# improvedThermoCoupleADC.net
KiCad netlist of a schematic drawn in EAGLE
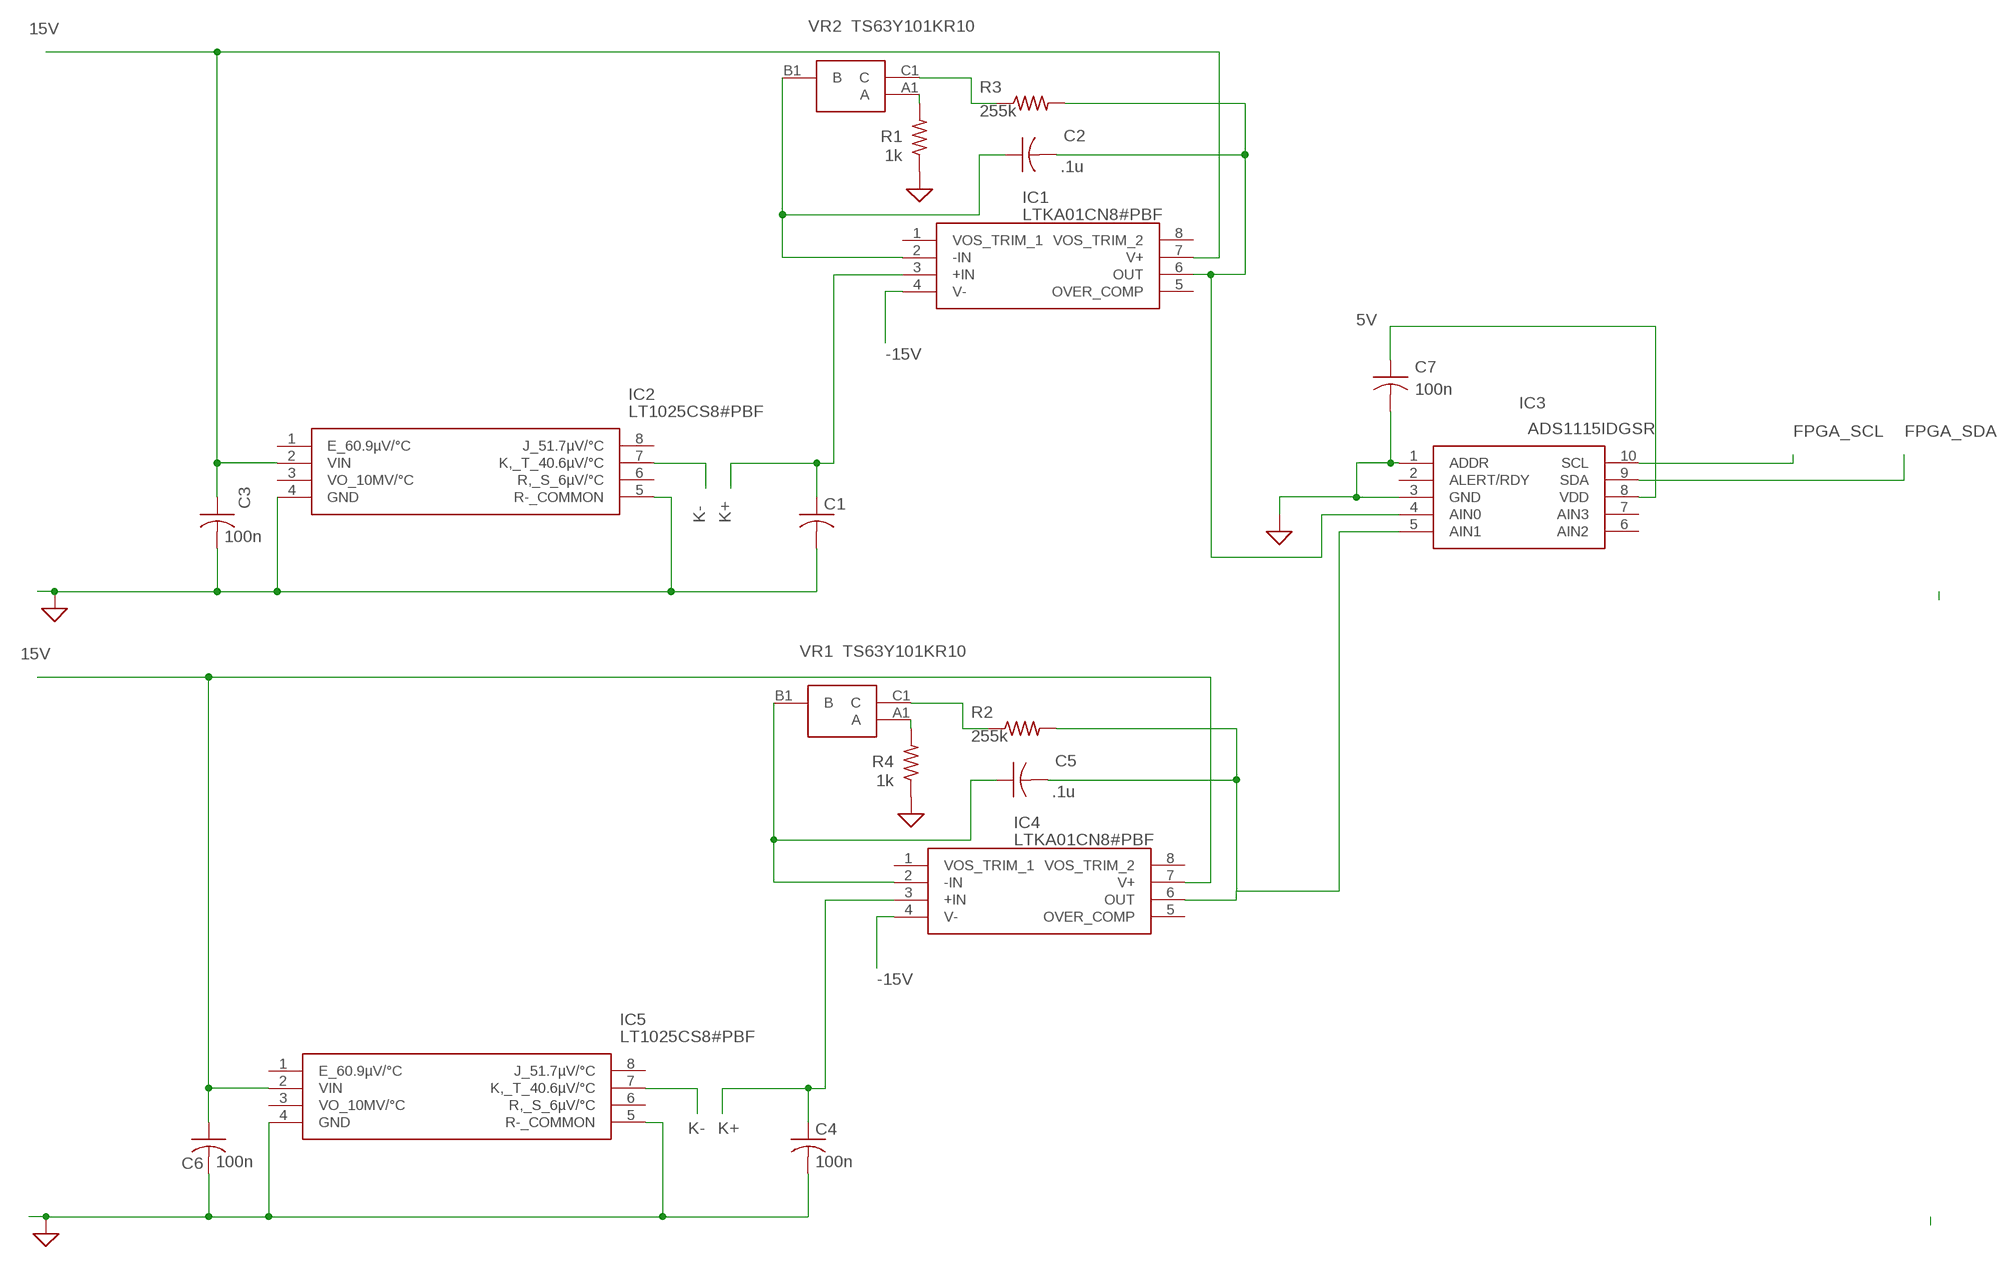
[diagram p0: schematic, sheet 1]

(export (version "E")
  (design (tool "Eeschema 10.0.6"))
  (components
    (comp (ref "C1")
      (value "C-USC0805")
      (footprint "eagle-import:C0805")
      (libsource (lib "eagle-import") (part "C-USC0805"))
    )
    (comp (ref "C2")
      (value ".1u")
      (footprint "eagle-import:C0805")
      (libsource (lib "eagle-import") (part "C-USC0805"))
    )
    (comp (ref "C3")
      (value "100n")
      (footprint "eagle-import:C0805")
      (libsource (lib "eagle-import") (part "C-USC0805"))
    )
    (comp (ref "C4")
      (value "100n")
      (footprint "eagle-import:C0805")
      (libsource (lib "eagle-import") (part "C-USC0805"))
    )
    (comp (ref "C5")
      (value ".1u")
      (footprint "eagle-import:C0805")
      (libsource (lib "eagle-import") (part "C-USC0805"))
    )
    (comp (ref "C6")
      (value "100n")
      (footprint "eagle-import:C0805")
      (libsource (lib "eagle-import") (part "C-USC0805"))
    )
    (comp (ref "C7")
      (value "100n")
      (footprint "eagle-import:C0805")
      (libsource (lib "eagle-import") (part "C-USC0805"))
    )
    (comp (ref "IC1")
      (value "LTKA01CN8#PBF")
      (footprint "eagle-import:DIP794W53P254L1016H394Q8N")
      (fields (field (name "MOUSER_PART_NUMBER") "584-LTKA01CN8#PBF"))
      (libsource (lib "eagle-import") (part "LTKA01CN8#PBF"))
    )
    (comp (ref "IC2")
      (value "LT1025CS8#PBF")
      (footprint "eagle-import:SOIC127P599X175-8N")
      (fields (field (name "MOUSER_PART_NUMBER") "584-LT1025CS8#PBF"))
      (libsource (lib "eagle-import") (part "LT1025CS8#PBF"))
    )
    (comp (ref "IC3")
      (value "ADS1115IDGSR")
      (footprint "eagle-import:SOP50P490X110-10N")
      (fields (field (name "MOUSER_PART_NUMBER") "595-ADS1115IDGSR"))
      (libsource (lib "eagle-import") (part "ADS1115IDGSR"))
    )
    (comp (ref "IC4")
      (value "LTKA01CN8#PBF")
      (footprint "eagle-import:DIP794W53P254L1016H394Q8N")
      (fields (field (name "MOUSER_PART_NUMBER") "584-LTKA01CN8#PBF"))
      (libsource (lib "eagle-import") (part "LTKA01CN8#PBF"))
    )
    (comp (ref "IC5")
      (value "LT1025CS8#PBF")
      (footprint "eagle-import:SOIC127P599X175-8N")
      (fields (field (name "MOUSER_PART_NUMBER") "584-LT1025CS8#PBF"))
      (libsource (lib "eagle-import") (part "LT1025CS8#PBF"))
    )
    (comp (ref "R1")
      (value "1k")
      (footprint "eagle-import:R0805")
      (libsource (lib "eagle-import") (part "R-US_R0805"))
    )
    (comp (ref "R2")
      (value "255k")
      (footprint "eagle-import:R0805")
      (libsource (lib "eagle-import") (part "R-US_R0805"))
    )
    (comp (ref "R3")
      (value "255k")
      (footprint "eagle-import:R0805")
      (libsource (lib "eagle-import") (part "R-US_R0805"))
    )
    (comp (ref "R4")
      (value "1k")
      (footprint "eagle-import:R0805")
      (libsource (lib "eagle-import") (part "R-US_R0805"))
    )
    (comp (ref "VR1")
      (value "TS63Y101KR10")
      (footprint "eagle-import:TS63Y203KR10")
      (fields (field (name "MOUSER_PART_NUMBER") "72-TS63Y101KR10"))
      (libsource (lib "eagle-import") (part "TS63Y101KR10"))
    )
    (comp (ref "VR2")
      (value "TS63Y101KR10")
      (footprint "eagle-import:TS63Y203KR10")
      (fields (field (name "MOUSER_PART_NUMBER") "72-TS63Y101KR10"))
      (libsource (lib "eagle-import") (part "TS63Y101KR10"))
    )
  )
  (nets
    (net (code "1") (name "/-15V") (class "Default")
      (node (ref "IC1") (pin "4") (pinfunction "V-_4") (pintype "bidirectional"))
      (node (ref "IC4") (pin "4") (pinfunction "V-_4") (pintype "bidirectional"))
    )
    (net (code "2") (name "/5V") (class "Default")
      (node (ref "C7") (pin "1") (pinfunction "1_1") (pintype "passive"))
      (node (ref "IC3") (pin "8") (pinfunction "VDD_8") (pintype "bidirectional"))
    )
    (net (code "3") (name "/15V") (class "Default")
      (node (ref "C3") (pin "1") (pinfunction "1_1") (pintype "passive"))
      (node (ref "C6") (pin "1") (pinfunction "1_1") (pintype "passive"))
      (node (ref "IC1") (pin "7") (pinfunction "V+_7") (pintype "bidirectional"))
      (node (ref "IC2") (pin "2") (pinfunction "VIN_2") (pintype "bidirectional"))
      (node (ref "IC4") (pin "7") (pinfunction "V+_7") (pintype "bidirectional"))
      (node (ref "IC5") (pin "2") (pinfunction "VIN_2") (pintype "bidirectional"))
    )
    (net (code "4") (name "/FPGA_SCL") (class "Default")
      (node (ref "IC3") (pin "10") (pinfunction "SCL_10") (pintype "bidirectional"))
    )
    (net (code "5") (name "/FPGA_SDA") (class "Default")
      (node (ref "IC3") (pin "9") (pinfunction "SDA_9") (pintype "bidirectional"))
    )
    (net (code "6") (name "/K+") (class "Default")
      (node (ref "C1") (pin "1") (pinfunction "1_1") (pintype "passive"))
      (node (ref "C4") (pin "1") (pinfunction "1_1") (pintype "passive"))
      (node (ref "IC1") (pin "3") (pinfunction "+IN_3") (pintype "bidirectional"))
      (node (ref "IC4") (pin "3") (pinfunction "+IN_3") (pintype "bidirectional"))
    )
    (net (code "7") (name "/K-") (class "Default")
      (node (ref "IC2") (pin "7") (pinfunction "K,_T_40.6µV/°C_7") (pintype "bidirectional"))
      (node (ref "IC5") (pin "7") (pinfunction "K,_T_40.6µV/°C_7") (pintype "bidirectional"))
    )
    (net (code "8") (name "Net-(IC1--IN)") (class "Default")
      (node (ref "C2") (pin "1") (pinfunction "1_1") (pintype "passive"))
      (node (ref "IC1") (pin "2") (pinfunction "-IN_2") (pintype "bidirectional"))
      (node (ref "VR2") (pin "B1") (pinfunction "B_B1") (pintype "bidirectional"))
    )
    (net (code "9") (name "Net-(IC1-OUT)") (class "Default")
      (node (ref "C2") (pin "2") (pinfunction "2_2") (pintype "passive"))
      (node (ref "IC1") (pin "6") (pinfunction "OUT_6") (pintype "bidirectional"))
      (node (ref "IC3") (pin "4") (pinfunction "AIN0_4") (pintype "bidirectional"))
      (node (ref "R3") (pin "2") (pinfunction "2_2") (pintype "passive"))
    )
    (net (code "10") (name "Net-(IC3-AIN1)") (class "Default")
      (node (ref "C5") (pin "2") (pinfunction "2_2") (pintype "passive"))
      (node (ref "IC3") (pin "5") (pinfunction "AIN1_5") (pintype "bidirectional"))
      (node (ref "IC4") (pin "6") (pinfunction "OUT_6") (pintype "bidirectional"))
      (node (ref "R2") (pin "2") (pinfunction "2_2") (pintype "passive"))
    )
    (net (code "11") (name "Net-(IC4--IN)") (class "Default")
      (node (ref "C5") (pin "1") (pinfunction "1_1") (pintype "passive"))
      (node (ref "IC4") (pin "2") (pinfunction "-IN_2") (pintype "bidirectional"))
      (node (ref "VR1") (pin "B1") (pinfunction "B_B1") (pintype "bidirectional"))
    )
    (net (code "12") (name "Net-(VR1-A)") (class "Default")
      (node (ref "R4") (pin "2") (pinfunction "2_2") (pintype "passive"))
      (node (ref "VR1") (pin "A1") (pinfunction "A_A1") (pintype "bidirectional"))
    )
    (net (code "13") (name "Net-(VR1-C)") (class "Default")
      (node (ref "R2") (pin "1") (pinfunction "1_1") (pintype "passive"))
      (node (ref "VR1") (pin "C1") (pinfunction "C_C1") (pintype "bidirectional"))
    )
    (net (code "14") (name "Net-(VR2-A)") (class "Default")
      (node (ref "R1") (pin "2") (pinfunction "2_2") (pintype "passive"))
      (node (ref "VR2") (pin "A1") (pinfunction "A_A1") (pintype "bidirectional"))
    )
    (net (code "15") (name "Net-(VR2-C)") (class "Default")
      (node (ref "R3") (pin "1") (pinfunction "1_1") (pintype "passive"))
      (node (ref "VR2") (pin "C1") (pinfunction "C_C1") (pintype "bidirectional"))
    )
    (net (code "16") (name "SUP") (class "Default")
      (node (ref "C1") (pin "2") (pinfunction "2_2") (pintype "passive"))
      (node (ref "C3") (pin "2") (pinfunction "2_2") (pintype "passive"))
      (node (ref "C4") (pin "2") (pinfunction "2_2") (pintype "passive"))
      (node (ref "C6") (pin "2") (pinfunction "2_2") (pintype "passive"))
      (node (ref "C7") (pin "2") (pinfunction "2_2") (pintype "passive"))
      (node (ref "IC2") (pin "4") (pinfunction "GND_4") (pintype "bidirectional"))
      (node (ref "IC2") (pin "5") (pinfunction "R-_COMMON_5") (pintype "bidirectional"))
      (node (ref "IC3") (pin "1") (pinfunction "ADDR_1") (pintype "bidirectional"))
      (node (ref "IC3") (pin "3") (pinfunction "GND_3") (pintype "bidirectional"))
      (node (ref "IC5") (pin "4") (pinfunction "GND_4") (pintype "bidirectional"))
      (node (ref "IC5") (pin "5") (pinfunction "R-_COMMON_5") (pintype "bidirectional"))
      (node (ref "R1") (pin "1") (pinfunction "1_1") (pintype "passive"))
      (node (ref "R4") (pin "1") (pinfunction "1_1") (pintype "passive"))
    )
    (net (code "17") (name "unconnected-(IC1-OVER_COMP-Pad5)") (class "Default")
      (node (ref "IC1") (pin "5") (pinfunction "OVER_COMP_5") (pintype "bidirectional"))
    )
    (net (code "18") (name "unconnected-(IC1-VOS_TRIM_1-Pad1)") (class "Default")
      (node (ref "IC1") (pin "1") (pinfunction "VOS_TRIM_1_1") (pintype "bidirectional"))
    )
    (net (code "19") (name "unconnected-(IC1-VOS_TRIM_2-Pad8)") (class "Default")
      (node (ref "IC1") (pin "8") (pinfunction "VOS_TRIM_2_8") (pintype "bidirectional"))
    )
    (net (code "20") (name "unconnected-(IC2-E_60.9µV{slash}°C-Pad1)") (class "Default")
      (node (ref "IC2") (pin "1") (pinfunction "E_60.9µV/°C_1") (pintype "bidirectional"))
    )
    (net (code "21") (name "unconnected-(IC2-J_51.7µV{slash}°C-Pad8)") (class "Default")
      (node (ref "IC2") (pin "8") (pinfunction "J_51.7µV/°C_8") (pintype "bidirectional"))
    )
    (net (code "22") (name "unconnected-(IC2-R,_S_6µV{slash}°C-Pad6)") (class "Default")
      (node (ref "IC2") (pin "6") (pinfunction "R,_S_6µV/°C_6") (pintype "bidirectional"))
    )
    (net (code "23") (name "unconnected-(IC2-VO_10MV{slash}°C-Pad3)") (class "Default")
      (node (ref "IC2") (pin "3") (pinfunction "VO_10MV/°C_3") (pintype "bidirectional"))
    )
    (net (code "24") (name "unconnected-(IC3-AIN2-Pad6)") (class "Default")
      (node (ref "IC3") (pin "6") (pinfunction "AIN2_6") (pintype "bidirectional"))
    )
    (net (code "25") (name "unconnected-(IC3-AIN3-Pad7)") (class "Default")
      (node (ref "IC3") (pin "7") (pinfunction "AIN3_7") (pintype "bidirectional"))
    )
    (net (code "26") (name "unconnected-(IC3-ALERT{slash}RDY-Pad2)") (class "Default")
      (node (ref "IC3") (pin "2") (pinfunction "ALERT/RDY_2") (pintype "bidirectional"))
    )
    (net (code "27") (name "unconnected-(IC4-OVER_COMP-Pad5)") (class "Default")
      (node (ref "IC4") (pin "5") (pinfunction "OVER_COMP_5") (pintype "bidirectional"))
    )
    (net (code "28") (name "unconnected-(IC4-VOS_TRIM_1-Pad1)") (class "Default")
      (node (ref "IC4") (pin "1") (pinfunction "VOS_TRIM_1_1") (pintype "bidirectional"))
    )
    (net (code "29") (name "unconnected-(IC4-VOS_TRIM_2-Pad8)") (class "Default")
      (node (ref "IC4") (pin "8") (pinfunction "VOS_TRIM_2_8") (pintype "bidirectional"))
    )
    (net (code "30") (name "unconnected-(IC5-E_60.9µV{slash}°C-Pad1)") (class "Default")
      (node (ref "IC5") (pin "1") (pinfunction "E_60.9µV/°C_1") (pintype "bidirectional"))
    )
    (net (code "31") (name "unconnected-(IC5-J_51.7µV{slash}°C-Pad8)") (class "Default")
      (node (ref "IC5") (pin "8") (pinfunction "J_51.7µV/°C_8") (pintype "bidirectional"))
    )
    (net (code "32") (name "unconnected-(IC5-R,_S_6µV{slash}°C-Pad6)") (class "Default")
      (node (ref "IC5") (pin "6") (pinfunction "R,_S_6µV/°C_6") (pintype "bidirectional"))
    )
    (net (code "33") (name "unconnected-(IC5-VO_10MV{slash}°C-Pad3)") (class "Default")
      (node (ref "IC5") (pin "3") (pinfunction "VO_10MV/°C_3") (pintype "bidirectional"))
    )
  )
)
